# COURONNE_PARTIE_II_SCHEMA.net
KiCad netlist of a schematic drawn in Altium Designer
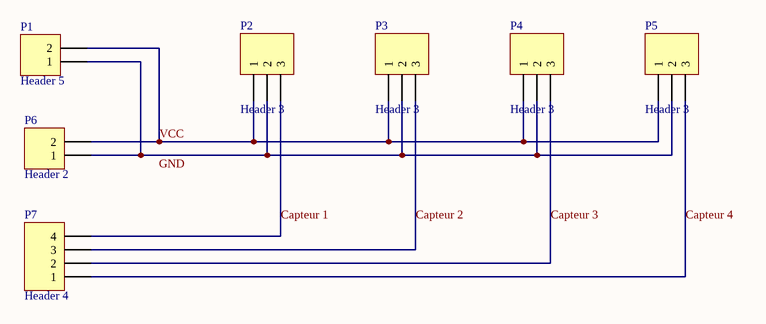
[diagram p0: COURONNE PARTIE II SCHEMA.SchDoc]

(export (version "E")
  (design (tool "Eeschema 10.0.6"))
  (components
    (comp (ref "P1")
      (value "Header 5")
      (footprint "HDR1X2")
      (description "Header, 2-Pin")
      (fields (field (name "PUBLISHER") "Altium Limited"))
      (libsource (lib "Miscellaneous Connectors") (part "Header 2"))
    )
    (comp (ref "P2")
      (value "Header 3")
      (footprint "HDR1X3")
      (description "Header, 3-Pin")
      (fields (field (name "PUBLISHER") "Altium Limited"))
      (libsource (lib "Miscellaneous Connectors") (part "Header 3"))
    )
    (comp (ref "P3")
      (value "Header 3")
      (footprint "HDR1X3")
      (description "Header, 3-Pin")
      (fields (field (name "PUBLISHER") "Altium Limited"))
      (libsource (lib "Miscellaneous Connectors") (part "Header 3"))
    )
    (comp (ref "P4")
      (value "Header 3")
      (footprint "HDR1X3")
      (description "Header, 3-Pin")
      (fields (field (name "PUBLISHER") "Altium Limited"))
      (libsource (lib "Miscellaneous Connectors") (part "Header 3"))
    )
    (comp (ref "P5")
      (value "Header 3")
      (footprint "HDR1X3")
      (description "Header, 3-Pin")
      (fields (field (name "PUBLISHER") "Altium Limited"))
      (libsource (lib "Miscellaneous Connectors") (part "Header 3"))
    )
    (comp (ref "P6")
      (value "Header 2")
      (footprint "HDR1X2")
      (description "Header, 2-Pin")
      (fields (field (name "PUBLISHER") "Altium Limited"))
      (libsource (lib "Miscellaneous Connectors") (part "Header 2"))
    )
    (comp (ref "P7")
      (value "Header 4")
      (footprint "HDR1X4")
      (description "Header, 4-Pin")
      (fields (field (name "PUBLISHER") "Altium Limited"))
      (libsource (lib "Miscellaneous Connectors") (part "Header 4"))
    )
  )
  (nets
    (net (code "1") (name "/Capteur 1") (class "Default")
      (node (ref "P2") (pin "3") (pinfunction "3_3") (pintype "passive"))
      (node (ref "P7") (pin "4") (pinfunction "4_4") (pintype "passive"))
    )
    (net (code "2") (name "/Capteur 2") (class "Default")
      (node (ref "P3") (pin "3") (pinfunction "3_3") (pintype "passive"))
      (node (ref "P7") (pin "3") (pinfunction "3_3") (pintype "passive"))
    )
    (net (code "3") (name "/Capteur 3") (class "Default")
      (node (ref "P4") (pin "3") (pinfunction "3_3") (pintype "passive"))
      (node (ref "P7") (pin "2") (pinfunction "2_2") (pintype "passive"))
    )
    (net (code "4") (name "/Capteur 4") (class "Default")
      (node (ref "P5") (pin "3") (pinfunction "3_3") (pintype "passive"))
      (node (ref "P7") (pin "1") (pinfunction "1_1") (pintype "passive"))
    )
    (net (code "5") (name "/GND") (class "Default")
      (node (ref "P1") (pin "1") (pinfunction "1_1") (pintype "passive"))
      (node (ref "P2") (pin "2") (pinfunction "2_2") (pintype "passive"))
      (node (ref "P3") (pin "2") (pinfunction "2_2") (pintype "passive"))
      (node (ref "P4") (pin "2") (pinfunction "2_2") (pintype "passive"))
      (node (ref "P5") (pin "2") (pinfunction "2_2") (pintype "passive"))
      (node (ref "P6") (pin "1") (pinfunction "1_1") (pintype "passive"))
    )
    (net (code "6") (name "/VCC") (class "Default")
      (node (ref "P1") (pin "2") (pinfunction "2_2") (pintype "passive"))
      (node (ref "P2") (pin "1") (pinfunction "1_1") (pintype "passive"))
      (node (ref "P3") (pin "1") (pinfunction "1_1") (pintype "passive"))
      (node (ref "P4") (pin "1") (pinfunction "1_1") (pintype "passive"))
      (node (ref "P5") (pin "1") (pinfunction "1_1") (pintype "passive"))
      (node (ref "P6") (pin "2") (pinfunction "2_2") (pintype "passive"))
    )
  )
)
